# CH32H417MEU6-UHSIF-Bottom-R0.net
KiCad netlist of a schematic drawn in Altium Designer
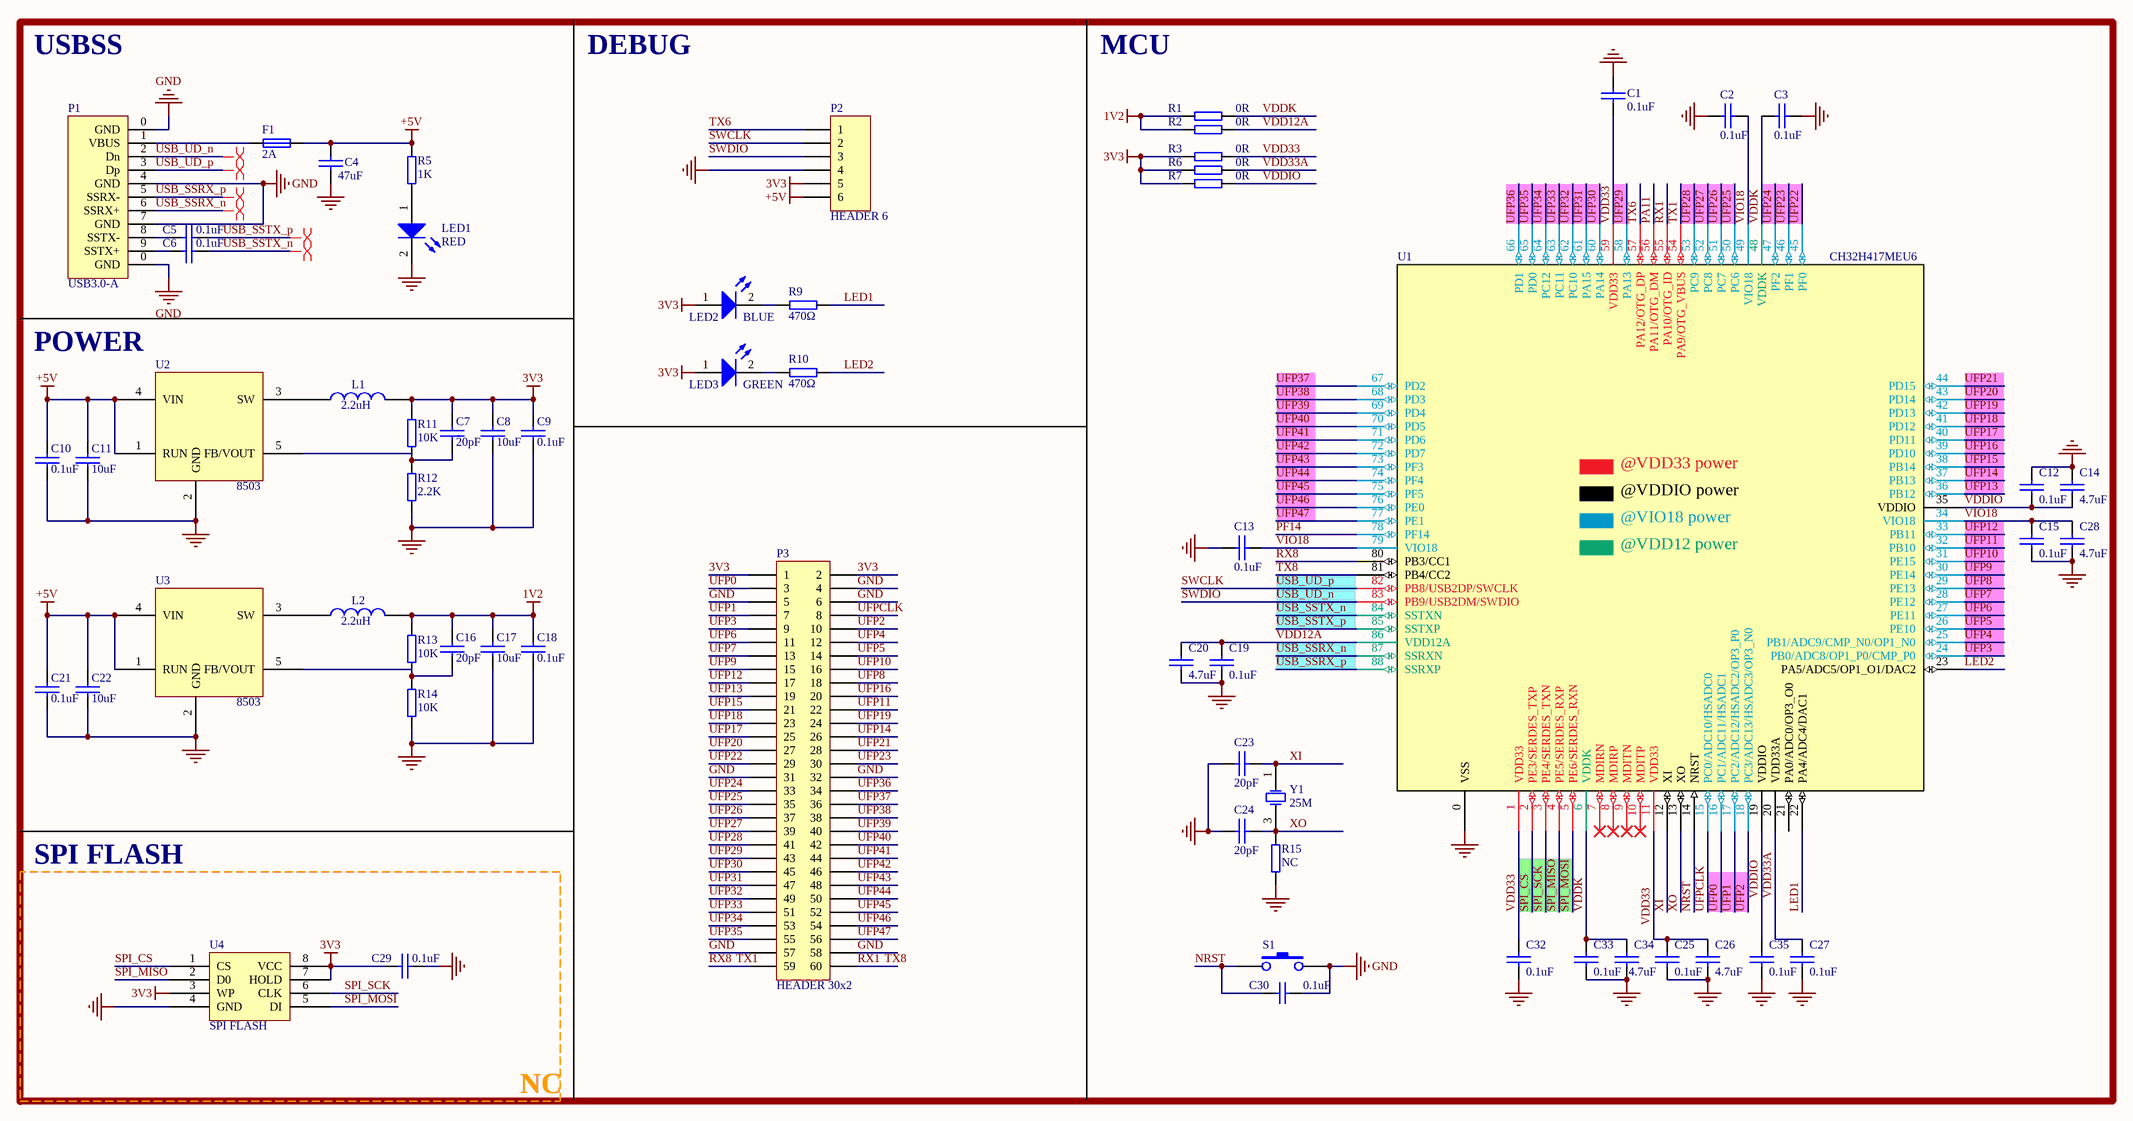
[diagram p0: CH32H417MEU6-UHSIF-Bottom-R0.SchDoc]

(export (version "E")
  (design (tool "Eeschema 10.0.6"))
  (components
    (comp (ref "C1")
      (value "0.1uF")
      (footprint "0402_C")
      (description "Capacitor")
      (libsource (lib "wch_sch_others") (part "CAP"))
    )
    (comp (ref "C2")
      (value "0.1uF")
      (footprint "0402_C")
      (description "Capacitor")
      (libsource (lib "wch_sch_others") (part "CAP"))
    )
    (comp (ref "C3")
      (value "0.1uF")
      (footprint "0402_C")
      (description "Capacitor")
      (libsource (lib "wch_sch_others") (part "CAP"))
    )
    (comp (ref "C4")
      (value "47uF")
      (footprint "3528_C")
      (description "Capacitor")
      (libsource (lib "wch_sch_others") (part "CAP"))
    )
    (comp (ref "C5")
      (value "0.1uF")
      (footprint "0402_C")
      (description "Capacitor")
      (libsource (lib "wch_sch_others") (part "CAP"))
    )
    (comp (ref "C6")
      (value "0.1uF")
      (footprint "0402_C")
      (description "Capacitor")
      (libsource (lib "wch_sch_others") (part "CAP"))
    )
    (comp (ref "C7")
      (value "20pF")
      (footprint "0402_C")
      (description "Capacitor")
      (libsource (lib "*") (part "CAP"))
    )
    (comp (ref "C8")
      (value "10uF")
      (footprint "0603_C")
      (description "Capacitor")
      (libsource (lib "") (part "CAP_1"))
    )
    (comp (ref "C9")
      (value "0.1uF")
      (footprint "0402_C")
      (description "Capacitor")
      (libsource (lib "*") (part "CAP"))
    )
    (comp (ref "C10")
      (value "0.1uF")
      (footprint "0402_C")
      (description "Capacitor")
      (libsource (lib "*") (part "CAP"))
    )
    (comp (ref "C11")
      (value "10uF")
      (footprint "0603_C")
      (description "Capacitor")
      (libsource (lib "") (part "CAP_1"))
    )
    (comp (ref "C12")
      (value "0.1uF")
      (footprint "0402_C")
      (description "Capacitor")
      (libsource (lib "wch_sch_others") (part "CAP"))
    )
    (comp (ref "C13")
      (value "0.1uF")
      (footprint "0402_C")
      (description "Capacitor")
      (libsource (lib "wch_sch_others") (part "CAP"))
    )
    (comp (ref "C14")
      (value "4.7uF")
      (footprint "0402_C")
      (description "Capacitor")
      (libsource (lib "wch_sch_others") (part "CAP"))
    )
    (comp (ref "C15")
      (value "0.1uF")
      (footprint "0402_C")
      (description "Capacitor")
      (libsource (lib "wch_sch_others") (part "CAP"))
    )
    (comp (ref "C16")
      (value "20pF")
      (footprint "0402_C")
      (description "Capacitor")
      (libsource (lib "*") (part "CAP"))
    )
    (comp (ref "C17")
      (value "10uF")
      (footprint "0603_C")
      (description "Capacitor")
      (libsource (lib "") (part "CAP_1"))
    )
    (comp (ref "C18")
      (value "0.1uF")
      (footprint "0402_C")
      (description "Capacitor")
      (libsource (lib "*") (part "CAP"))
    )
    (comp (ref "C19")
      (value "0.1uF")
      (footprint "0402_C")
      (description "Capacitor")
      (libsource (lib "wch_sch_others") (part "CAP"))
    )
    (comp (ref "C20")
      (value "4.7uF")
      (footprint "0402_C")
      (description "Capacitor")
      (libsource (lib "wch_sch_others") (part "CAP"))
    )
    (comp (ref "C21")
      (value "0.1uF")
      (footprint "0402_C")
      (description "Capacitor")
      (libsource (lib "*") (part "CAP"))
    )
    (comp (ref "C22")
      (value "10uF")
      (footprint "0603_C")
      (description "Capacitor")
      (libsource (lib "") (part "CAP_1"))
    )
    (comp (ref "C23")
      (value "20pF")
      (footprint "0402_C")
      (description "Capacitor")
      (libsource (lib "wch_sch_others") (part "CAP"))
    )
    (comp (ref "C24")
      (value "20pF")
      (footprint "0402_C")
      (description "Capacitor")
      (libsource (lib "wch_sch_others") (part "CAP"))
    )
    (comp (ref "C25")
      (value "0.1uF")
      (footprint "0402_C")
      (description "Capacitor")
      (libsource (lib "wch_sch_others") (part "CAP"))
    )
    (comp (ref "C26")
      (value "4.7uF")
      (footprint "0402_C")
      (description "Capacitor")
      (libsource (lib "wch_sch_others") (part "CAP"))
    )
    (comp (ref "C27")
      (value "0.1uF")
      (footprint "0402_C")
      (description "Capacitor")
      (libsource (lib "wch_sch_others") (part "CAP"))
    )
    (comp (ref "C28")
      (value "4.7uF")
      (footprint "0402_C")
      (description "Capacitor")
      (libsource (lib "wch_sch_others") (part "CAP"))
    )
    (comp (ref "C29")
      (value "0.1uF")
      (footprint "0402_C")
      (description "Capacitor")
      (libsource (lib "wch_sch_others") (part "CAP"))
    )
    (comp (ref "C30")
      (value "0.1uF")
      (footprint "0402_C")
      (description "Capacitor")
      (libsource (lib "Miscellaneous Devices") (part "Cap"))
    )
    (comp (ref "C32")
      (value "0.1uF")
      (footprint "0402_C")
      (description "Capacitor")
      (libsource (lib "wch_sch_others") (part "CAP"))
    )
    (comp (ref "C33")
      (value "0.1uF")
      (footprint "0402_C")
      (description "Capacitor")
      (libsource (lib "wch_sch_others") (part "CAP"))
    )
    (comp (ref "C34")
      (value "4.7uF")
      (footprint "0402_C")
      (description "Capacitor")
      (libsource (lib "wch_sch_others") (part "CAP"))
    )
    (comp (ref "C35")
      (value "0.1uF")
      (footprint "0402_C")
      (description "Capacitor")
      (libsource (lib "wch_sch_others") (part "CAP"))
    )
    (comp (ref "F1")
      (value "2A")
      (footprint "0805")
      (description "Fuse")
      (libsource (lib "wch_sch_others") (part "FUSE1"))
    )
    (comp (ref "L1") (value "2.2uH") (footprint "CD32") (libsource (lib "*") (part "INDUCTOR")))
    (comp (ref "L2") (value "2.2uH") (footprint "CD32") (libsource (lib "*") (part "INDUCTOR")))
    (comp (ref "LED1")
      (value "RED")
      (footprint "MYPCB:0603+")
      (description "Typical INFRARED GaAs LED")
      (libsource (lib "wch_sch_others") (part "LED"))
    )
    (comp (ref "LED2")
      (value "BLUE")
      (footprint "MYPCB:0603+")
      (description "Typical INFRARED GaAs LED")
      (libsource (lib "wch_sch_others") (part "LED"))
    )
    (comp (ref "LED3")
      (value "GREEN")
      (footprint "MYPCB:0603+")
      (description "Typical INFRARED GaAs LED")
      (libsource (lib "wch_sch_others") (part "LED"))
    )
    (comp (ref "P1")
      (value "USB3.0-A")
      (footprint "USB3.0-A-Receptacle")
      (libsource (lib "wch_sch_others") (part "USB3.0-A"))
    )
    (comp (ref "P2")
      (value "HEADER 6")
      (footprint "SIP6-2.54mm")
      (description "Header, 6-Pin")
      (libsource (lib "wch_sch_others") (part "HEADER 6"))
    )
    (comp (ref "P3")
      (value "HEADER 30x2")
      (footprint "MYPCB:BTB-60P-P0.5-MR")
      (description "Header, 30-Pin, Dual row")
      (libsource (lib "wch_sch_others") (part "HEADER 30x2"))
    )
    (comp (ref "R1") (value "0R") (footprint "0603") (libsource (lib "wch_sch_others") (part "RES")))
    (comp (ref "R2") (value "0R") (footprint "0603") (libsource (lib "wch_sch_others") (part "RES")))
    (comp (ref "R3") (value "0R") (footprint "0603") (libsource (lib "wch_sch_others") (part "RES")))
    (comp (ref "R5") (value "1K") (footprint "0402") (libsource (lib "wch_sch_others") (part "RES")))
    (comp (ref "R6") (value "0R") (footprint "0603") (libsource (lib "wch_sch_others") (part "RES")))
    (comp (ref "R7") (value "0R") (footprint "0603") (libsource (lib "wch_sch_others") (part "RES")))
    (comp (ref "R9") (value "470Ω") (footprint "0402") (libsource (lib "wch_sch_others") (part "RES")))
    (comp (ref "R10") (value "470Ω") (footprint "0402") (libsource (lib "wch_sch_others") (part "RES")))
    (comp (ref "R11") (value "10K") (footprint "0402") (libsource (lib "*") (part "R")))
    (comp (ref "R12") (value "2.2K") (footprint "0402") (libsource (lib "*") (part "R")))
    (comp (ref "R13") (value "10K") (footprint "0402") (libsource (lib "*") (part "R")))
    (comp (ref "R14") (value "10K") (footprint "0402") (libsource (lib "*") (part "R")))
    (comp (ref "R15") (value "NC") (footprint "0402") (libsource (lib "*") (part "RES")))
    (comp (ref "S1") (value "~") (footprint "贴片按键") (libsource (lib "wch_sch_others") (part "KEY1")))
    (comp (ref "U1")
      (value "CH32H417MEU6")
      (footprint "QFN88_10X10")
      (description "RISC-V FPU HD-MCU, 384MHz, USB3.0 & PD, 100M Ethernet, DVP, SDMMC, QSPI, OPA, ADC, DAC")
      (libsource (lib "DHXXXSCH") (part "CH32H417MEU6"))
    )
    (comp (ref "U2") (value "8503") (footprint "SOT-23-5") (libsource (lib "*") (part "FP6160")))
    (comp (ref "U3") (value "8503") (footprint "SOT-23-5") (libsource (lib "*") (part "FP6160")))
    (comp (ref "U4")
      (value "SPI FLASH")
      (footprint "SOIC-8_208mil")
      (libsource (lib "wch_sch_others") (part "W25Q64"))
    )
    (comp (ref "Y1")
      (value "25M")
      (footprint "XT3225")
      (description "Crystal Oscillator")
      (fields (field (name "PUBLISHER") "Altium Limited"))
      (libsource (lib "Miscellaneous Devices") (part "XTAL"))
    )
  )
  (nets
    (net (code "1") (name "+5V") (class "Default")
      (node (ref "C10") (pin "2") (pinfunction "2_2") (pintype "passive"))
      (node (ref "C11") (pin "2") (pinfunction "2_2") (pintype "passive"))
      (node (ref "C21") (pin "2") (pinfunction "2_2") (pintype "passive"))
      (node (ref "C22") (pin "2") (pinfunction "2_2") (pintype "passive"))
      (node (ref "C4") (pin "1") (pinfunction "1_1") (pintype "passive"))
      (node (ref "F1") (pin "2") (pintype "passive"))
      (node (ref "P2") (pin "6") (pinfunction "6_6") (pintype "passive"))
      (node (ref "R5") (pin "2") (pintype "passive"))
      (node (ref "U2") (pin "1") (pinfunction "RUN_1") (pintype "passive"))
      (node (ref "U2") (pin "4") (pinfunction "VIN_4") (pintype "passive"))
      (node (ref "U3") (pin "1") (pinfunction "RUN_1") (pintype "passive"))
      (node (ref "U3") (pin "4") (pinfunction "VIN_4") (pintype "passive"))
    )
    (net (code "2") (name "/LED1") (class "Default")
      (node (ref "R9") (pin "1") (pintype "passive"))
      (node (ref "U1") (pin "22") (pinfunction "PA4/ADC4/DAC1_22") (pintype "bidirectional"))
    )
    (net (code "3") (name "/LED2") (class "Default")
      (node (ref "R10") (pin "1") (pintype "passive"))
      (node (ref "U1") (pin "23") (pinfunction "PA5/ADC5/OP1_O1/DAC2_23") (pintype "bidirectional"))
    )
    (net (code "4") (name "/NRST") (class "Default")
      (node (ref "C30") (pin "2") (pinfunction "2_2") (pintype "passive"))
      (node (ref "S1") (pin "1") (pinfunction "1_1") (pintype "passive"))
      (node (ref "U1") (pin "14") (pinfunction "NRST_14") (pintype "input"))
    )
    (net (code "5") (name "/PA11") (class "Default")
      (node (ref "U1") (pin "56") (pinfunction "PA11/OTG_DM_56") (pintype "bidirectional"))
    )
    (net (code "6") (name "/PF14") (class "Default")
      (node (ref "U1") (pin "78") (pinfunction "PF14_78") (pintype "bidirectional"))
    )
    (net (code "7") (name "/RX1") (class "Default")
      (node (ref "P3") (pin "60") (pinfunction "60_60") (pintype "passive"))
      (node (ref "U1") (pin "55") (pinfunction "PA10/OTG_ID_55") (pintype "bidirectional"))
      (node (ref "U1") (pin "81") (pinfunction "PB4/CC2_81") (pintype "bidirectional"))
    )
    (net (code "8") (name "/RX8") (class "Default")
      (node (ref "P3") (pin "59") (pinfunction "59_59") (pintype "passive"))
      (node (ref "U1") (pin "54") (pinfunction "PA9/OTG_VBUS_54") (pintype "bidirectional"))
      (node (ref "U1") (pin "80") (pinfunction "PB3/CC1_80") (pintype "bidirectional"))
    )
    (net (code "9") (name "/SPI_CS") (class "Default")
      (node (ref "U1") (pin "2") (pinfunction "PE3/SERDES_TXP_2") (pintype "bidirectional"))
      (node (ref "U4") (pin "1") (pinfunction "CS_1") (pintype "passive"))
    )
    (net (code "10") (name "/SPI_MISO") (class "Default")
      (node (ref "U1") (pin "4") (pinfunction "PE5/SERDES_RXP_4") (pintype "bidirectional"))
      (node (ref "U4") (pin "2") (pinfunction "D0_2") (pintype "passive"))
    )
    (net (code "11") (name "/SPI_MOSI") (class "Default")
      (node (ref "U1") (pin "5") (pinfunction "PE6/SERDES_RXN_5") (pintype "bidirectional"))
      (node (ref "U4") (pin "5") (pinfunction "DI_5") (pintype "passive"))
    )
    (net (code "12") (name "/SPI_SCK") (class "Default")
      (node (ref "U1") (pin "3") (pinfunction "PE4/SERDES_TXN_3") (pintype "bidirectional"))
      (node (ref "U4") (pin "6") (pinfunction "CLK_6") (pintype "passive"))
    )
    (net (code "13") (name "/SWCLK") (class "Default")
      (node (ref "P1") (pin "3") (pinfunction "Dp_3") (pintype "passive"))
      (node (ref "P2") (pin "2") (pinfunction "2_2") (pintype "passive"))
      (node (ref "U1") (pin "82") (pinfunction "PB8/USB2DP/SWCLK_82") (pintype "bidirectional"))
    )
    (net (code "14") (name "/SWDIO") (class "Default")
      (node (ref "P1") (pin "2") (pinfunction "Dn_2") (pintype "passive"))
      (node (ref "P2") (pin "3") (pinfunction "3_3") (pintype "passive"))
      (node (ref "U1") (pin "83") (pinfunction "PB9/USB2DM/SWDIO_83") (pintype "bidirectional"))
    )
    (net (code "15") (name "/TX6") (class "Default")
      (node (ref "P2") (pin "1") (pinfunction "1_1") (pintype "passive"))
      (node (ref "U1") (pin "57") (pinfunction "PA12/OTG_DP_57") (pintype "bidirectional"))
    )
    (net (code "16") (name "/UFP0") (class "Default")
      (node (ref "P3") (pin "3") (pinfunction "3_3") (pintype "passive"))
      (node (ref "U1") (pin "16") (pinfunction "PC1/ADC11/HSADC1_16") (pintype "bidirectional"))
    )
    (net (code "17") (name "/UFP1") (class "Default")
      (node (ref "P3") (pin "7") (pinfunction "7_7") (pintype "passive"))
      (node (ref "U1") (pin "17") (pinfunction "PC2/ADC12/HSADC2/OP3_P0_17") (pintype "bidirectional"))
    )
    (net (code "18") (name "/UFP2") (class "Default")
      (node (ref "P3") (pin "10") (pinfunction "10_10") (pintype "passive"))
      (node (ref "U1") (pin "18") (pinfunction "PC3/ADC13/HSADC3/OP3_N0_18") (pintype "bidirectional"))
    )
    (net (code "19") (name "/UFP3") (class "Default")
      (node (ref "P3") (pin "9") (pinfunction "9_9") (pintype "passive"))
      (node (ref "U1") (pin "24") (pinfunction "PB0/ADC8/OP1_P0/CMP_P0_24") (pintype "bidirectional"))
    )
    (net (code "20") (name "/UFP4") (class "Default")
      (node (ref "P3") (pin "12") (pinfunction "12_12") (pintype "passive"))
      (node (ref "U1") (pin "25") (pinfunction "PB1/ADC9/CMP_N0/OP1_N0_25") (pintype "bidirectional"))
    )
    (net (code "21") (name "/UFP5") (class "Default")
      (node (ref "P3") (pin "14") (pinfunction "14_14") (pintype "passive"))
      (node (ref "U1") (pin "26") (pinfunction "PE10_26") (pintype "bidirectional"))
    )
    (net (code "22") (name "/UFP6") (class "Default")
      (node (ref "P3") (pin "11") (pinfunction "11_11") (pintype "passive"))
      (node (ref "U1") (pin "27") (pinfunction "PE11_27") (pintype "bidirectional"))
    )
    (net (code "23") (name "/UFP7") (class "Default")
      (node (ref "P3") (pin "13") (pinfunction "13_13") (pintype "passive"))
      (node (ref "U1") (pin "28") (pinfunction "PE12_28") (pintype "bidirectional"))
    )
    (net (code "24") (name "/UFP8") (class "Default")
      (node (ref "P3") (pin "18") (pinfunction "18_18") (pintype "passive"))
      (node (ref "U1") (pin "29") (pinfunction "PE13_29") (pintype "bidirectional"))
    )
    (net (code "25") (name "/UFP9") (class "Default")
      (node (ref "P3") (pin "15") (pinfunction "15_15") (pintype "passive"))
      (node (ref "U1") (pin "30") (pinfunction "PE14_30") (pintype "bidirectional"))
    )
    (net (code "26") (name "/UFP10") (class "Default")
      (node (ref "P3") (pin "16") (pinfunction "16_16") (pintype "passive"))
      (node (ref "U1") (pin "31") (pinfunction "PE15_31") (pintype "bidirectional"))
    )
    (net (code "27") (name "/UFP11") (class "Default")
      (node (ref "P3") (pin "22") (pinfunction "22_22") (pintype "passive"))
      (node (ref "U1") (pin "32") (pinfunction "PB10_32") (pintype "bidirectional"))
    )
    (net (code "28") (name "/UFP12") (class "Default")
      (node (ref "P3") (pin "17") (pinfunction "17_17") (pintype "passive"))
      (node (ref "U1") (pin "33") (pinfunction "PB11_33") (pintype "bidirectional"))
    )
    (net (code "29") (name "/UFP13") (class "Default")
      (node (ref "P3") (pin "19") (pinfunction "19_19") (pintype "passive"))
      (node (ref "U1") (pin "36") (pinfunction "PB12_36") (pintype "bidirectional"))
    )
    (net (code "30") (name "/UFP14") (class "Default")
      (node (ref "P3") (pin "26") (pinfunction "26_26") (pintype "passive"))
      (node (ref "U1") (pin "37") (pinfunction "PB13_37") (pintype "bidirectional"))
    )
    (net (code "31") (name "/UFP15") (class "Default")
      (node (ref "P3") (pin "21") (pinfunction "21_21") (pintype "passive"))
      (node (ref "U1") (pin "38") (pinfunction "PB14_38") (pintype "bidirectional"))
    )
    (net (code "32") (name "/UFP16") (class "Default")
      (node (ref "P3") (pin "20") (pinfunction "20_20") (pintype "passive"))
      (node (ref "U1") (pin "39") (pinfunction "PD10_39") (pintype "bidirectional"))
    )
    (net (code "33") (name "/UFP17") (class "Default")
      (node (ref "P3") (pin "25") (pinfunction "25_25") (pintype "passive"))
      (node (ref "U1") (pin "40") (pinfunction "PD11_40") (pintype "bidirectional"))
    )
    (net (code "34") (name "/UFP18") (class "Default")
      (node (ref "P3") (pin "23") (pinfunction "23_23") (pintype "passive"))
      (node (ref "U1") (pin "41") (pinfunction "PD12_41") (pintype "bidirectional"))
    )
    (net (code "35") (name "/UFP19") (class "Default")
      (node (ref "P3") (pin "24") (pinfunction "24_24") (pintype "passive"))
      (node (ref "U1") (pin "42") (pinfunction "PD13_42") (pintype "bidirectional"))
    )
    (net (code "36") (name "/UFP20") (class "Default")
      (node (ref "P3") (pin "27") (pinfunction "27_27") (pintype "passive"))
      (node (ref "U1") (pin "43") (pinfunction "PD14_43") (pintype "bidirectional"))
    )
    (net (code "37") (name "/UFP21") (class "Default")
      (node (ref "P3") (pin "28") (pinfunction "28_28") (pintype "passive"))
      (node (ref "U1") (pin "44") (pinfunction "PD15_44") (pintype "bidirectional"))
    )
    (net (code "38") (name "/UFP22") (class "Default")
      (node (ref "P3") (pin "29") (pinfunction "29_29") (pintype "passive"))
      (node (ref "U1") (pin "45") (pinfunction "PF0_45") (pintype "bidirectional"))
    )
    (net (code "39") (name "/UFP23") (class "Default")
      (node (ref "P3") (pin "30") (pinfunction "30_30") (pintype "passive"))
      (node (ref "U1") (pin "46") (pinfunction "PF1_46") (pintype "bidirectional"))
    )
    (net (code "40") (name "/UFP24") (class "Default")
      (node (ref "P3") (pin "33") (pinfunction "33_33") (pintype "passive"))
      (node (ref "U1") (pin "47") (pinfunction "PF2_47") (pintype "bidirectional"))
    )
    (net (code "41") (name "/UFP25") (class "Default")
      (node (ref "P3") (pin "35") (pinfunction "35_35") (pintype "passive"))
      (node (ref "U1") (pin "50") (pinfunction "PC6_50") (pintype "bidirectional"))
    )
    (net (code "42") (name "/UFP26") (class "Default")
      (node (ref "P3") (pin "37") (pinfunction "37_37") (pintype "passive"))
      (node (ref "U1") (pin "51") (pinfunction "PC7_51") (pintype "bidirectional"))
    )
    (net (code "43") (name "/UFP27") (class "Default")
      (node (ref "P3") (pin "39") (pinfunction "39_39") (pintype "passive"))
      (node (ref "U1") (pin "52") (pinfunction "PC8_52") (pintype "bidirectional"))
    )
    (net (code "44") (name "/UFP28") (class "Default")
      (node (ref "P3") (pin "41") (pinfunction "41_41") (pintype "passive"))
      (node (ref "U1") (pin "53") (pinfunction "PC9_53") (pintype "bidirectional"))
    )
    (net (code "45") (name "/UFP29") (class "Default")
      (node (ref "P3") (pin "43") (pinfunction "43_43") (pintype "passive"))
      (node (ref "U1") (pin "58") (pinfunction "PA13_58") (pintype "bidirectional"))
    )
    (net (code "46") (name "/UFP30") (class "Default")
      (node (ref "P3") (pin "45") (pinfunction "45_45") (pintype "passive"))
      (node (ref "U1") (pin "60") (pinfunction "PA14_60") (pintype "bidirectional"))
    )
    (net (code "47") (name "/UFP31") (class "Default")
      (node (ref "P3") (pin "47") (pinfunction "47_47") (pintype "passive"))
      (node (ref "U1") (pin "61") (pinfunction "PA15_61") (pintype "bidirectional"))
    )
    (net (code "48") (name "/UFP32") (class "Default")
      (node (ref "P3") (pin "49") (pinfunction "49_49") (pintype "passive"))
      (node (ref "U1") (pin "62") (pinfunction "PC10_62") (pintype "bidirectional"))
    )
    (net (code "49") (name "/UFP33") (class "Default")
      (node (ref "P3") (pin "51") (pinfunction "51_51") (pintype "passive"))
      (node (ref "U1") (pin "63") (pinfunction "PC11_63") (pintype "bidirectional"))
    )
    (net (code "50") (name "/UFP34") (class "Default")
      (node (ref "P3") (pin "53") (pinfunction "53_53") (pintype "passive"))
      (node (ref "U1") (pin "64") (pinfunction "PC12_64") (pintype "bidirectional"))
    )
    (net (code "51") (name "/UFP35") (class "Default")
      (node (ref "P3") (pin "55") (pinfunction "55_55") (pintype "passive"))
      (node (ref "U1") (pin "65") (pinfunction "PD0_65") (pintype "bidirectional"))
    )
    (net (code "52") (name "/UFP36") (class "Default")
      (node (ref "P3") (pin "34") (pinfunction "34_34") (pintype "passive"))
      (node (ref "U1") (pin "66") (pinfunction "PD1_66") (pintype "bidirectional"))
    )
    (net (code "53") (name "/UFP37") (class "Default")
      (node (ref "P3") (pin "36") (pinfunction "36_36") (pintype "passive"))
      (node (ref "U1") (pin "67") (pinfunction "PD2_67") (pintype "bidirectional"))
    )
    (net (code "54") (name "/UFP38") (class "Default")
      (node (ref "P3") (pin "38") (pinfunction "38_38") (pintype "passive"))
      (node (ref "U1") (pin "68") (pinfunction "PD3_68") (pintype "bidirectional"))
    )
    (net (code "55") (name "/UFP39") (class "Default")
      (node (ref "P3") (pin "40") (pinfunction "40_40") (pintype "passive"))
      (node (ref "U1") (pin "69") (pinfunction "PD4_69") (pintype "bidirectional"))
    )
    (net (code "56") (name "/UFP40") (class "Default")
      (node (ref "P3") (pin "42") (pinfunction "42_42") (pintype "passive"))
      (node (ref "U1") (pin "70") (pinfunction "PD5_70") (pintype "bidirectional"))
    )
    (net (code "57") (name "/UFP41") (class "Default")
      (node (ref "P3") (pin "44") (pinfunction "44_44") (pintype "passive"))
      (node (ref "U1") (pin "71") (pinfunction "PD6_71") (pintype "bidirectional"))
    )
    (net (code "58") (name "/UFP42") (class "Default")
      (node (ref "P3") (pin "46") (pinfunction "46_46") (pintype "passive"))
      (node (ref "U1") (pin "72") (pinfunction "PD7_72") (pintype "bidirectional"))
    )
    (net (code "59") (name "/UFP43") (class "Default")
      (node (ref "P3") (pin "48") (pinfunction "48_48") (pintype "passive"))
      (node (ref "U1") (pin "73") (pinfunction "PF3_73") (pintype "bidirectional"))
    )
    (net (code "60") (name "/UFP44") (class "Default")
      (node (ref "P3") (pin "50") (pinfunction "50_50") (pintype "passive"))
      (node (ref "U1") (pin "74") (pinfunction "PF4_74") (pintype "bidirectional"))
    )
    (net (code "61") (name "/UFP45") (class "Default")
      (node (ref "P3") (pin "52") (pinfunction "52_52") (pintype "passive"))
      (node (ref "U1") (pin "75") (pinfunction "PF5_75") (pintype "bidirectional"))
    )
    (net (code "62") (name "/UFP46") (class "Default")
      (node (ref "P3") (pin "54") (pinfunction "54_54") (pintype "passive"))
      (node (ref "U1") (pin "76") (pinfunction "PE0_76") (pintype "bidirectional"))
    )
    (net (code "63") (name "/UFP47") (class "Default")
      (node (ref "P3") (pin "56") (pinfunction "56_56") (pintype "passive"))
      (node (ref "U1") (pin "77") (pinfunction "PE1_77") (pintype "bidirectional"))
    )
    (net (code "64") (name "/UFPCLK") (class "Default")
      (node (ref "P3") (pin "8") (pinfunction "8_8") (pintype "passive"))
      (node (ref "U1") (pin "15") (pinfunction "PC0/ADC10/HSADC0_15") (pintype "bidirectional"))
    )
    (net (code "65") (name "/USB_SSRX_n") (class "Default")
      (node (ref "P1") (pin "6") (pinfunction "SSRX+_6") (pintype "passive"))
      (node (ref "U1") (pin "87") (pinfunction "SSRXN_87") (pintype "bidirectional"))
    )
    (net (code "66") (name "/USB_SSRX_p") (class "Default")
      (node (ref "P1") (pin "5") (pinfunction "SSRX-_5") (pintype "passive"))
      (node (ref "U1") (pin "88") (pinfunction "SSRXP_88") (pintype "bidirectional"))
    )
    (net (code "67") (name "/USB_SSTX_n") (class "Default")
      (node (ref "C6") (pin "1") (pinfunction "1_1") (pintype "passive"))
      (node (ref "U1") (pin "84") (pinfunction "SSTXN_84") (pintype "bidirectional"))
    )
    (net (code "68") (name "/USB_SSTX_p") (class "Default")
      (node (ref "C5") (pin "1") (pinfunction "1_1") (pintype "passive"))
      (node (ref "U1") (pin "85") (pinfunction "SSTXP_85") (pintype "bidirectional"))
    )
    (net (code "69") (name "/VDD12A") (class "Default")
      (node (ref "C19") (pin "2") (pinfunction "2_2") (pintype "passive"))
      (node (ref "C20") (pin "2") (pinfunction "2_2") (pintype "passive"))
      (node (ref "R2") (pin "1") (pintype "passive"))
      (node (ref "U1") (pin "86") (pinfunction "VDD12A_86") (pintype "power_in"))
    )
    (net (code "70") (name "/VDD33") (class "Default")
      (node (ref "C1") (pin "1") (pinfunction "1_1") (pintype "passive"))
      (node (ref "C25") (pin "2") (pinfunction "2_2") (pintype "passive"))
      (node (ref "C26") (pin "2") (pinfunction "2_2") (pintype "passive"))
      (node (ref "C32") (pin "2") (pinfunction "2_2") (pintype "passive"))
      (node (ref "R3") (pin "1") (pintype "passive"))
      (node (ref "U1") (pin "1") (pinfunction "VDD33_1") (pintype "power_in"))
      (node (ref "U1") (pin "11") (pinfunction "VDD33_11") (pintype "power_in"))
      (node (ref "U1") (pin "59") (pinfunction "VDD33_59") (pintype "power_in"))
    )
    (net (code "71") (name "/VDD33A") (class "Default")
      (node (ref "C27") (pin "2") (pinfunction "2_2") (pintype "passive"))
      (node (ref "R6") (pin "1") (pintype "passive"))
      (node (ref "U1") (pin "20") (pinfunction "VDD33A_20") (pintype "power_in"))
    )
    (net (code "72") (name "/VDDIO") (class "Default")
      (node (ref "C12") (pin "1") (pinfunction "1_1") (pintype "passive"))
      (node (ref "C14") (pin "1") (pinfunction "1_1") (pintype "passive"))
      (node (ref "C35") (pin "2") (pinfunction "2_2") (pintype "passive"))
      (node (ref "R7") (pin "1") (pintype "passive"))
      (node (ref "U1") (pin "19") (pinfunction "VDDIO_19") (pintype "power_in"))
      (node (ref "U1") (pin "35") (pinfunction "VDDIO_35") (pintype "power_in"))
    )
    (net (code "73") (name "/VDDK") (class "Default")
      (node (ref "C3") (pin "2") (pinfunction "2_2") (pintype "passive"))
      (node (ref "C33") (pin "2") (pinfunction "2_2") (pintype "passive"))
      (node (ref "C34") (pin "2") (pinfunction "2_2") (pintype "passive"))
      (node (ref "R1") (pin "1") (pintype "passive"))
      (node (ref "U1") (pin "48") (pinfunction "VDDK_48") (pintype "power_in"))
      (node (ref "U1") (pin "6") (pinfunction "VDDK_6") (pintype "power_in"))
    )
    (net (code "74") (name "/VIO18") (class "Default")
      (node (ref "C13") (pin "1") (pinfunction "1_1") (pintype "passive"))
      (node (ref "C15") (pin "2") (pinfunction "2_2") (pintype "passive"))
      (node (ref "C2") (pin "1") (pinfunction "1_1") (pintype "passive"))
      (node (ref "C28") (pin "2") (pinfunction "2_2") (pintype "passive"))
      (node (ref "U1") (pin "34") (pinfunction "VIO18_34") (pintype "power_in"))
      (node (ref "U1") (pin "49") (pinfunction "VIO18_49") (pintype "power_in"))
      (node (ref "U1") (pin "79") (pinfunction "VIO18_79") (pintype "power_in"))
    )
    (net (code "75") (name "/XI") (class "Default")
      (node (ref "C23") (pin "2") (pinfunction "2_2") (pintype "passive"))
      (node (ref "U1") (pin "12") (pinfunction "XI_12") (pintype "bidirectional"))
      (node (ref "Y1") (pin "1") (pinfunction "OSC1_1") (pintype "passive"))
    )
    (net (code "76") (name "/XO") (class "Default")
      (node (ref "C24") (pin "2") (pinfunction "2_2") (pintype "passive"))
      (node (ref "R15") (pin "2") (pintype "passive"))
      (node (ref "U1") (pin "13") (pinfunction "XO_13") (pintype "bidirectional"))
      (node (ref "Y1") (pin "3") (pinfunction "OSC2_3") (pintype "passive"))
    )
    (net (code "77") (name "1V2") (class "Default")
      (node (ref "C16") (pin "1") (pinfunction "1_1") (pintype "passive"))
      (node (ref "C17") (pin "2") (pinfunction "2_2") (pintype "passive"))
      (node (ref "C18") (pin "2") (pinfunction "2_2") (pintype "passive"))
      (node (ref "L2") (pin "2") (pinfunction "2_2") (pintype "passive"))
      (node (ref "R1") (pin "2") (pintype "passive"))
      (node (ref "R13") (pin "1") (pinfunction "1_1") (pintype "passive"))
      (node (ref "R2") (pin "2") (pintype "passive"))
    )
    (net (code "78") (name "3V3") (class "Default")
      (node (ref "C29") (pin "2") (pinfunction "2_2") (pintype "passive"))
      (node (ref "C7") (pin "1") (pinfunction "1_1") (pintype "passive"))
      (node (ref "C8") (pin "2") (pinfunction "2_2") (pintype "passive"))
      (node (ref "C9") (pin "2") (pinfunction "2_2") (pintype "passive"))
      (node (ref "L1") (pin "2") (pinfunction "2_2") (pintype "passive"))
      (node (ref "LED2") (pin "1") (pinfunction "A_1") (pintype "passive"))
      (node (ref "LED3") (pin "1") (pinfunction "A_1") (pintype "passive"))
      (node (ref "P2") (pin "5") (pinfunction "5_5") (pintype "passive"))
      (node (ref "P3") (pin "1") (pinfunction "1_1") (pintype "passive"))
      (node (ref "P3") (pin "2") (pinfunction "2_2") (pintype "passive"))
      (node (ref "R11") (pin "1") (pinfunction "1_1") (pintype "passive"))
      (node (ref "R3") (pin "2") (pintype "passive"))
      (node (ref "R6") (pin "2") (pintype "passive"))
      (node (ref "R7") (pin "2") (pintype "passive"))
      (node (ref "U4") (pin "3") (pinfunction "WP_3") (pintype "passive"))
      (node (ref "U4") (pin "7") (pinfunction "HOLD_7") (pintype "passive"))
      (node (ref "U4") (pin "8") (pinfunction "VCC_8") (pintype "passive"))
    )
    (net (code "79") (name "GND") (class "Default")
      (node (ref "C1") (pin "2") (pinfunction "2_2") (pintype "passive"))
      (node (ref "C10") (pin "1") (pinfunction "1_1") (pintype "passive"))
      (node (ref "C11") (pin "1") (pinfunction "1_1") (pintype "passive"))
      (node (ref "C12") (pin "2") (pinfunction "2_2") (pintype "passive"))
      (node (ref "C13") (pin "2") (pinfunction "2_2") (pintype "passive"))
      (node (ref "C14") (pin "2") (pinfunction "2_2") (pintype "passive"))
      (node (ref "C15") (pin "1") (pinfunction "1_1") (pintype "passive"))
      (node (ref "C17") (pin "1") (pinfunction "1_1") (pintype "passive"))
      (node (ref "C18") (pin "1") (pinfunction "1_1") (pintype "passive"))
      (node (ref "C19") (pin "1") (pinfunction "1_1") (pintype "passive"))
      (node (ref "C2") (pin "2") (pinfunction "2_2") (pintype "passive"))
      (node (ref "C20") (pin "1") (pinfunction "1_1") (pintype "passive"))
      (node (ref "C21") (pin "1") (pinfunction "1_1") (pintype "passive"))
      (node (ref "C22") (pin "1") (pinfunction "1_1") (pintype "passive"))
      (node (ref "C23") (pin "1") (pinfunction "1_1") (pintype "passive"))
      (node (ref "C24") (pin "1") (pinfunction "1_1") (pintype "passive"))
      (node (ref "C25") (pin "1") (pinfunction "1_1") (pintype "passive"))
      (node (ref "C26") (pin "1") (pinfunction "1_1") (pintype "passive"))
      (node (ref "C27") (pin "1") (pinfunction "1_1") (pintype "passive"))
      (node (ref "C28") (pin "1") (pinfunction "1_1") (pintype "passive"))
      (node (ref "C29") (pin "1") (pinfunction "1_1") (pintype "passive"))
      (node (ref "C3") (pin "1") (pinfunction "1_1") (pintype "passive"))
      (node (ref "C30") (pin "1") (pinfunction "1_1") (pintype "passive"))
      (node (ref "C32") (pin "1") (pinfunction "1_1") (pintype "passive"))
      (node (ref "C33") (pin "1") (pinfunction "1_1") (pintype "passive"))
      (node (ref "C34") (pin "1") (pinfunction "1_1") (pintype "passive"))
      (node (ref "C35") (pin "1") (pinfunction "1_1") (pintype "passive"))
      (node (ref "C4") (pin "2") (pinfunction "2_2") (pintype "passive"))
      (node (ref "C8") (pin "1") (pinfunction "1_1") (pintype "passive"))
      (node (ref "C9") (pin "1") (pinfunction "1_1") (pintype "passive"))
      (node (ref "LED1") (pin "2") (pinfunction "K_2") (pintype "passive"))
      (node (ref "P1") (pin "0") (pinfunction "GND_0") (pintype "passive"))
      (node (ref "P1") (pin "4") (pinfunction "GND_4") (pintype "passive"))
      (node (ref "P1") (pin "7") (pinfunction "GND_7") (pintype "passive"))
      (node (ref "P2") (pin "4") (pinfunction "4_4") (pintype "passive"))
      (node (ref "P3") (pin "31") (pinfunction "31_31") (pintype "passive"))
      (node (ref "P3") (pin "32") (pinfunction "32_32") (pintype "passive"))
      (node (ref "P3") (pin "4") (pinfunction "4_4") (pintype "passive"))
      (node (ref "P3") (pin "5") (pinfunction "5_5") (pintype "passive"))
      (node (ref "P3") (pin "57") (pinfunction "57_57") (pintype "passive"))
      (node (ref "P3") (pin "58") (pinfunction "58_58") (pintype "passive"))
      (node (ref "P3") (pin "6") (pinfunction "6_6") (pintype "passive"))
      (node (ref "R12") (pin "1") (pinfunction "1_1") (pintype "passive"))
      (node (ref "R14") (pin "1") (pinfunction "1_1") (pintype "passive"))
      (node (ref "R15") (pin "1") (pintype "passive"))
      (node (ref "S1") (pin "2") (pinfunction "2_2") (pintype "passive"))
      (node (ref "U1") (pin "0") (pinfunction "VSS_0") (pintype "power_in"))
      (node (ref "U2") (pin "2") (pinfunction "GND_2") (pintype "passive"))
      (node (ref "U3") (pin "2") (pinfunction "GND_2") (pintype "passive"))
      (node (ref "U4") (pin "4") (pinfunction "GND_4") (pintype "passive"))
    )
    (net (code "80") (name "Net-(LED1-A)") (class "Default")
      (node (ref "LED1") (pin "1") (pinfunction "A_1") (pintype "passive"))
      (node (ref "R5") (pin "1") (pintype "passive"))
    )
    (net (code "81") (name "Net-(LED2-K)") (class "Default")
      (node (ref "LED2") (pin "2") (pinfunction "K_2") (pintype "passive"))
      (node (ref "R9") (pin "2") (pintype "passive"))
    )
    (net (code "82") (name "Net-(LED3-K)") (class "Default")
      (node (ref "LED3") (pin "2") (pinfunction "K_2") (pintype "passive"))
      (node (ref "R10") (pin "2") (pintype "passive"))
    )
    (net (code "83") (name "Net-(P1-SSTX+)") (class "Default")
      (node (ref "C6") (pin "2") (pinfunction "2_2") (pintype "passive"))
      (node (ref "P1") (pin "9") (pinfunction "SSTX+_9") (pintype "passive"))
    )
    (net (code "84") (name "Net-(P1-SSTX-)") (class "Default")
      (node (ref "C5") (pin "2") (pinfunction "2_2") (pintype "passive"))
      (node (ref "P1") (pin "8") (pinfunction "SSTX-_8") (pintype "passive"))
    )
    (net (code "85") (name "Net-(P1-VBUS)") (class "Default")
      (node (ref "F1") (pin "1") (pintype "passive"))
      (node (ref "P1") (pin "1") (pinfunction "VBUS_1") (pintype "passive"))
    )
    (net (code "86") (name "Net-(U2-FB{slash}VOUT)") (class "Default")
      (node (ref "C7") (pin "2") (pinfunction "2_2") (pintype "passive"))
      (node (ref "R11") (pin "2") (pinfunction "2_2") (pintype "passive"))
      (node (ref "R12") (pin "2") (pinfunction "2_2") (pintype "passive"))
      (node (ref "U2") (pin "5") (pinfunction "FB/VOUT_5") (pintype "passive"))
    )
    (net (code "87") (name "Net-(U2-SW)") (class "Default")
      (node (ref "L1") (pin "1") (pinfunction "1_1") (pintype "passive"))
      (node (ref "U2") (pin "3") (pinfunction "SW_3") (pintype "passive"))
    )
    (net (code "88") (name "Net-(U3-FB{slash}VOUT)") (class "Default")
      (node (ref "C16") (pin "2") (pinfunction "2_2") (pintype "passive"))
      (node (ref "R13") (pin "2") (pinfunction "2_2") (pintype "passive"))
      (node (ref "R14") (pin "2") (pinfunction "2_2") (pintype "passive"))
      (node (ref "U3") (pin "5") (pinfunction "FB/VOUT_5") (pintype "passive"))
    )
    (net (code "89") (name "Net-(U3-SW)") (class "Default")
      (node (ref "L2") (pin "1") (pinfunction "1_1") (pintype "passive"))
      (node (ref "U3") (pin "3") (pinfunction "SW_3") (pintype "passive"))
    )
    (net (code "90") (name "unconnected-(U1-MDIRN-Pad7)") (class "Default")
      (node (ref "U1") (pin "7") (pinfunction "MDIRN_7") (pintype "bidirectional+no_connect"))
    )
    (net (code "91") (name "unconnected-(U1-MDIRP-Pad8)") (class "Default")
      (node (ref "U1") (pin "8") (pinfunction "MDIRP_8") (pintype "bidirectional+no_connect"))
    )
    (net (code "92") (name "unconnected-(U1-MDITN-Pad9)") (class "Default")
      (node (ref "U1") (pin "9") (pinfunction "MDITN_9") (pintype "bidirectional+no_connect"))
    )
    (net (code "93") (name "unconnected-(U1-MDITP-Pad10)") (class "Default")
      (node (ref "U1") (pin "10") (pinfunction "MDITP_10") (pintype "bidirectional+no_connect"))
    )
    (net (code "94") (name "unconnected-(U1-PA0{slash}ADC0{slash}OP3_O0-Pad21)") (class "Default")
      (node (ref "U1") (pin "21") (pinfunction "PA0/ADC0/OP3_O0_21") (pintype "bidirectional"))
    )
  )
)
